# MAX30102_Adapter_SCH.net
KiCad netlist of a schematic drawn in Altium Designer
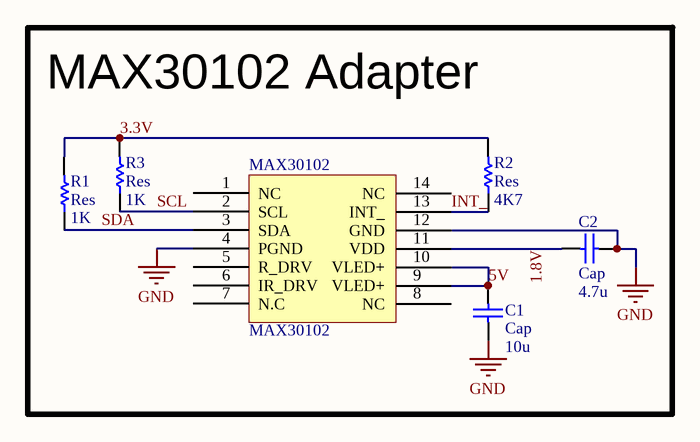
[diagram p0: MAX30102_Adapter_SCH.SchDoc]

(export (version "E")
  (design (tool "Eeschema 10.0.6"))
  (components
    (comp (ref "C1")
      (value "Cap")
      (footprint "0603 Cap")
      (fields (field (name "ALTIUM_VALUE") "10u"))
      (libsource (lib "B105rlc") (part "Cap"))
    )
    (comp (ref "C2")
      (value "Cap")
      (footprint "0603 Cap")
      (fields (field (name "ALTIUM_VALUE") "4.7u"))
      (libsource (lib "B105rlc") (part "Cap"))
    )
    (comp (ref "MAX30102")
      (value "MAX30102")
      (footprint "MAX30102")
      (libsource (lib "MAX30102_Adapter") (part "MAX30102"))
    )
    (comp (ref "R1")
      (value "Res")
      (footprint "0603 Res")
      (fields (field (name "ALTIUM_VALUE") "1K"))
      (libsource (lib "B105rlc") (part "Res"))
    )
    (comp (ref "R2")
      (value "Res")
      (footprint "0603 Res")
      (fields (field (name "ALTIUM_VALUE") "4K7"))
      (libsource (lib "B105rlc") (part "Res"))
    )
    (comp (ref "R3")
      (value "Res")
      (footprint "0603 Res")
      (fields (field (name "ALTIUM_VALUE") "1K"))
      (libsource (lib "B105rlc") (part "Res"))
    )
  )
  (nets
    (net (code "1") (name "/1.8V") (class "Default")
      (node (ref "C2") (pin "2") (pinfunction "2_2") (pintype "passive"))
      (node (ref "MAX30102") (pin "11") (pinfunction "VDD_11") (pintype "passive"))
    )
    (net (code "2") (name "/3.3V") (class "Default")
      (node (ref "R1") (pin "2") (pinfunction "2_2") (pintype "passive"))
      (node (ref "R2") (pin "2") (pinfunction "2_2") (pintype "passive"))
      (node (ref "R3") (pin "2") (pinfunction "2_2") (pintype "passive"))
    )
    (net (code "3") (name "/5V") (class "Default")
      (node (ref "C1") (pin "1") (pinfunction "1_1") (pintype "passive"))
      (node (ref "MAX30102") (pin "10") (pinfunction "VLED+_10") (pintype "passive"))
      (node (ref "MAX30102") (pin "9") (pinfunction "VLED+_9") (pintype "passive"))
    )
    (net (code "4") (name "/INT_") (class "Default")
      (node (ref "MAX30102") (pin "13") (pinfunction "INT__13") (pintype "passive"))
      (node (ref "R2") (pin "1") (pinfunction "1_1") (pintype "passive"))
    )
    (net (code "5") (name "/SCL") (class "Default")
      (node (ref "MAX30102") (pin "2") (pinfunction "SCL_2") (pintype "passive"))
      (node (ref "R3") (pin "1") (pinfunction "1_1") (pintype "passive"))
    )
    (net (code "6") (name "/SDA") (class "Default")
      (node (ref "MAX30102") (pin "3") (pinfunction "SDA_3") (pintype "passive"))
      (node (ref "R1") (pin "1") (pinfunction "1_1") (pintype "passive"))
    )
    (net (code "7") (name "GND") (class "Default")
      (node (ref "C1") (pin "2") (pinfunction "2_2") (pintype "passive"))
      (node (ref "C2") (pin "1") (pinfunction "1_1") (pintype "passive"))
      (node (ref "MAX30102") (pin "12") (pinfunction "GND_12") (pintype "passive"))
      (node (ref "MAX30102") (pin "4") (pinfunction "PGND_4") (pintype "passive"))
    )
    (net (code "8") (name "unconnected-(MAX30102-IR_DRV-Pad6)") (class "Default")
      (node (ref "MAX30102") (pin "6") (pinfunction "IR_DRV_6") (pintype "passive"))
    )
    (net (code "9") (name "unconnected-(MAX30102-N.C-Pad7)") (class "Default")
      (node (ref "MAX30102") (pin "7") (pinfunction "N.C_7") (pintype "passive"))
    )
    (net (code "10") (name "unconnected-(MAX30102-NC-Pad1)") (class "Default")
      (node (ref "MAX30102") (pin "1") (pinfunction "NC_1") (pintype "passive"))
    )
    (net (code "11") (name "unconnected-(MAX30102-NC-Pad8)") (class "Default")
      (node (ref "MAX30102") (pin "8") (pinfunction "NC_8") (pintype "passive"))
    )
    (net (code "12") (name "unconnected-(MAX30102-NC-Pad14)") (class "Default")
      (node (ref "MAX30102") (pin "14") (pinfunction "NC_14") (pintype "passive"))
    )
    (net (code "13") (name "unconnected-(MAX30102-R_DRV-Pad5)") (class "Default")
      (node (ref "MAX30102") (pin "5") (pinfunction "R_DRV_5") (pintype "passive"))
    )
  )
)
